# 05_-_POWER.net
KiCad netlist of a schematic drawn in Altium Designer
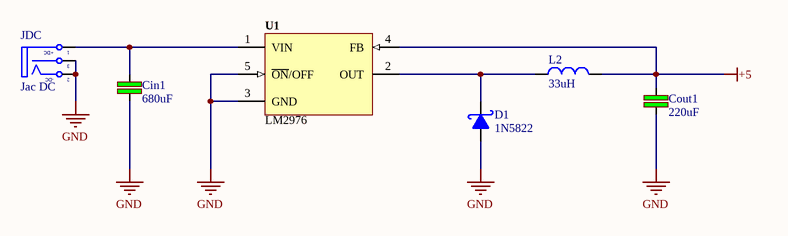
[diagram p0: [05] - POWER.SchDoc]

(export (version "E")
  (design (tool "Eeschema 10.0.6"))
  (components
    (comp (ref "Cin1")
      (value "680uF")
      (footprint "CAP_D10")
      (description "Cap np  1pF - 472pF")
      (libsource (lib "My Library") (part "CAP"))
    )
    (comp (ref "Cout1")
      (value "220uF")
      (footprint "CAP_D10")
      (description "Cap np  1pF - 472pF")
      (libsource (lib "My Library") (part "CAP"))
    )
    (comp (ref "D1")
      (value "1N5822")
      (footprint "SMA")
      (description "Schottky Rectifiers")
      (libsource (lib "My Library") (part "1N5822"))
    )
    (comp (ref "JDC")
      (value "Jac DC")
      (footprint "DC-IN")
      (description "Jac DC input")
      (libsource (lib "My Library") (part "DCIN"))
    )
    (comp (ref "L2")
      (value "33uH")
      (footprint "L-SMD-M-7.3x4.5")
      (description "Inductor")
      (libsource (lib "My Library") (part "Inductor"))
    )
    (comp (ref "U1") (value "LM2976") (footprint "TO-263") (libsource (lib "My Library") (part "LM2596")))
  )
  (nets
    (net (code "1") (name "+5") (class "Default")
      (node (ref "Cout1") (pin "2") (pinfunction "2_2") (pintype "passive"))
      (node (ref "L2") (pin "2") (pinfunction "2_2") (pintype "passive"))
      (node (ref "U1") (pin "4") (pinfunction "FB_4") (pintype "input"))
    )
    (net (code "2") (name "GND") (class "Default")
      (node (ref "Cin1") (pin "1") (pinfunction "1_1") (pintype "passive"))
      (node (ref "Cout1") (pin "1") (pinfunction "1_1") (pintype "passive"))
      (node (ref "D1") (pin "1") (pinfunction "A_1") (pintype "passive"))
      (node (ref "JDC") (pin "2") (pinfunction "TN_2") (pintype "passive"))
      (node (ref "JDC") (pin "3") (pinfunction "S_3") (pintype "power_in"))
      (node (ref "U1") (pin "3") (pinfunction "GND_3") (pintype "power_in"))
      (node (ref "U1") (pin "5") (pinfunction "~{ON}/OFF_5") (pintype "input"))
    )
    (net (code "3") (name "Net-(D1-K)") (class "Default")
      (node (ref "D1") (pin "2") (pinfunction "K_2") (pintype "passive"))
      (node (ref "L2") (pin "1") (pinfunction "1_1") (pintype "passive"))
      (node (ref "U1") (pin "2") (pinfunction "OUT_2") (pintype "power_in"))
    )
    (net (code "4") (name "Net-(JDC-T)") (class "Default")
      (node (ref "Cin1") (pin "2") (pinfunction "2_2") (pintype "passive"))
      (node (ref "JDC") (pin "1") (pinfunction "T_1") (pintype "passive"))
      (node (ref "U1") (pin "1") (pinfunction "VIN_1") (pintype "power_in"))
    )
  )
)
